# board.net
KiCad netlist of a schematic drawn in EAGLE
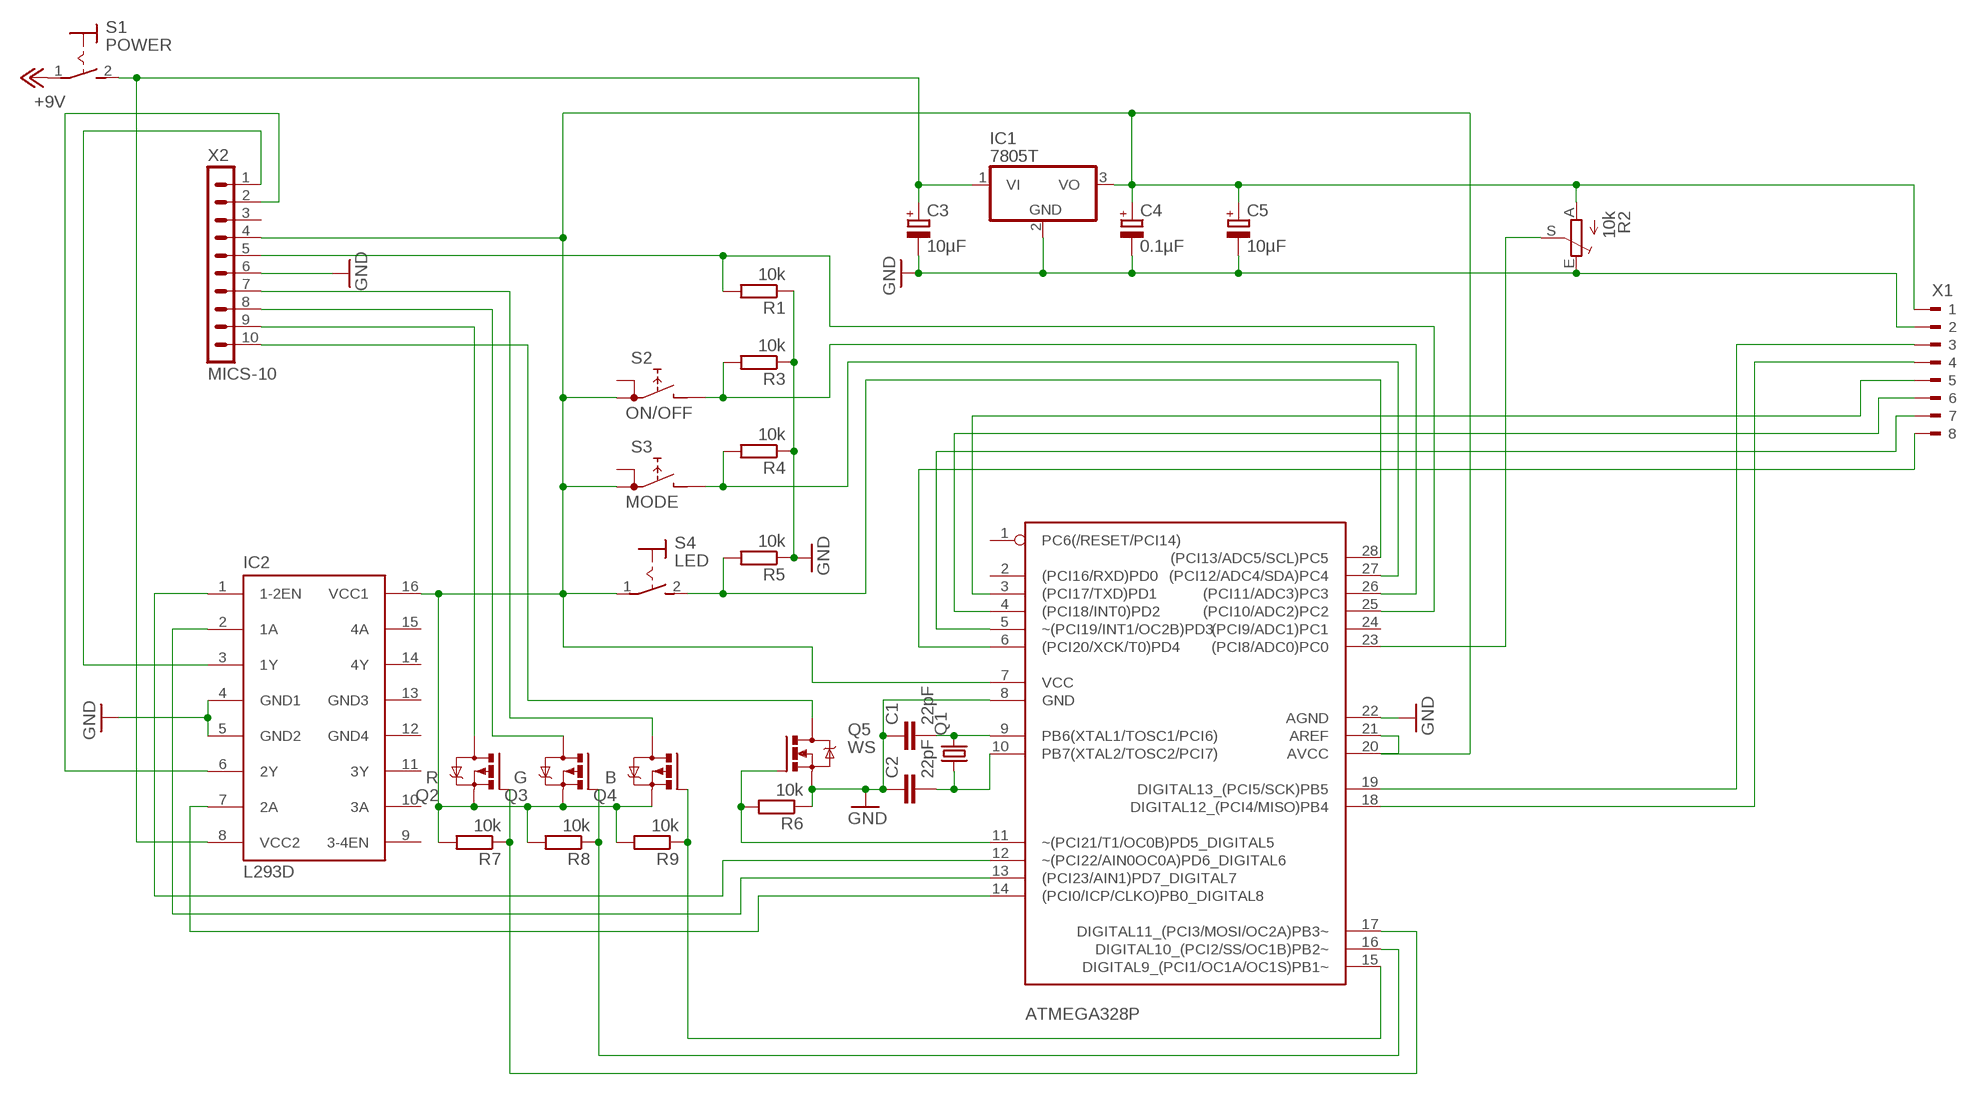
[diagram p0: schematic, sheet 1]

(export (version "E")
  (design (tool "Eeschema 10.0.6"))
  (components
    (comp (ref "ATMEGA328P")
      (value "ATMEGA328-20P")
      (footprint "eagle-import:DIL28-3")
      (libsource (lib "eagle-import") (part "ATMEGA328P-20"))
    )
    (comp (ref "C1")
      (value "22pF")
      (footprint "eagle-import:C2.5-2")
      (libsource (lib "eagle-import") (part "C2.5/2"))
    )
    (comp (ref "C2")
      (value "22pF")
      (footprint "eagle-import:C2.5-2")
      (libsource (lib "eagle-import") (part "C2.5/2"))
    )
    (comp (ref "C3")
      (value "10µF")
      (footprint "eagle-import:E2,5-5")
      (libsource (lib "eagle-import") (part "CPOL-EUE2.5-5"))
    )
    (comp (ref "C4")
      (value "0.1µF")
      (footprint "eagle-import:E2,5-5")
      (libsource (lib "eagle-import") (part "CPOL-EUE2.5-5"))
    )
    (comp (ref "C5")
      (value "10µF")
      (footprint "eagle-import:E2,5-5")
      (libsource (lib "eagle-import") (part "CPOL-EUE2.5-5"))
    )
    (comp (ref "IC1")
      (value "7805T")
      (footprint "eagle-import:TO220H")
      (libsource (lib "eagle-import") (part "78T05"))
    )
    (comp (ref "IC2")
      (value "L293D")
      (footprint "eagle-import:DIL16")
      (libsource (lib "eagle-import") (part "L293D"))
    )
    (comp (ref "Q1")
      (value "CRYSTALHC49S")
      (footprint "eagle-import:HC49_S")
      (libsource (lib "eagle-import") (part "CRYSTALHC49S"))
    )
    (comp (ref "Q2")
      (value "R")
      (footprint "eagle-import:I-PAK_TO251AA")
      (libsource (lib "eagle-import") (part "IRF?5305U"))
    )
    (comp (ref "Q3")
      (value "G")
      (footprint "eagle-import:I-PAK_TO251AA")
      (libsource (lib "eagle-import") (part "IRF?5305U"))
    )
    (comp (ref "Q4")
      (value "B")
      (footprint "eagle-import:I-PAK_TO251AA")
      (libsource (lib "eagle-import") (part "IRF?5305U"))
    )
    (comp (ref "Q5")
      (value "WS")
      (footprint "eagle-import:TO220BH")
      (libsource (lib "eagle-import") (part "IRFZ48Z"))
    )
    (comp (ref "R1")
      (value "10k")
      (footprint "eagle-import:0204_5")
      (libsource (lib "eagle-import") (part "R-EU_0204/5"))
    )
    (comp (ref "R2")
      (value "10k")
      (footprint "eagle-import:ECP10S")
      (libsource (lib "eagle-import") (part "TRIM_EU-ECP10S"))
    )
    (comp (ref "R3")
      (value "10k")
      (footprint "eagle-import:0204_5")
      (libsource (lib "eagle-import") (part "R-EU_0204/5"))
    )
    (comp (ref "R4")
      (value "10k")
      (footprint "eagle-import:0204_5")
      (libsource (lib "eagle-import") (part "R-EU_0204/5"))
    )
    (comp (ref "R5")
      (value "10k")
      (footprint "eagle-import:0204_5")
      (libsource (lib "eagle-import") (part "R-EU_0204/5"))
    )
    (comp (ref "R6")
      (value "10k")
      (footprint "eagle-import:0204_5")
      (libsource (lib "eagle-import") (part "R-EU_0204/5"))
    )
    (comp (ref "R7")
      (value "10k")
      (footprint "eagle-import:0204_5")
      (libsource (lib "eagle-import") (part "R-EU_0204/5"))
    )
    (comp (ref "R8")
      (value "10k")
      (footprint "eagle-import:0204_5")
      (libsource (lib "eagle-import") (part "R-EU_0204/5"))
    )
    (comp (ref "R9")
      (value "10k")
      (footprint "eagle-import:0204_5")
      (libsource (lib "eagle-import") (part "R-EU_0204/5"))
    )
    (comp (ref "S1")
      (value "POWER")
      (footprint "eagle-import:MS243")
      (libsource (lib "eagle-import") (part "MS243"))
    )
    (comp (ref "S2")
      (value "ON/OFF")
      (footprint "eagle-import:RDT1034")
      (libsource (lib "eagle-import") (part "RDT1034"))
    )
    (comp (ref "S3")
      (value "MODE")
      (footprint "eagle-import:RDT1034")
      (libsource (lib "eagle-import") (part "RDT1034"))
    )
    (comp (ref "S4")
      (value "LED")
      (footprint "eagle-import:MS243")
      (libsource (lib "eagle-import") (part "MS243"))
    )
    (comp (ref "X1")
      (value "90F-8")
      (footprint "eagle-import:90F-8")
      (libsource (lib "eagle-import") (part "90F-8"))
    )
    (comp (ref "X2")
      (value "MICS-10")
      (footprint "eagle-import:MICS-10")
      (libsource (lib "eagle-import") (part "MICS-10"))
    )
  )
  (nets
    (net (code "1") (name "+9V") (class "Default")
      (node (ref "S1") (pin "1") (pinfunction "P_1") (pintype "passive"))
    )
    (net (code "2") (name "/GND3") (class "Default")
      (node (ref "IC2") (pin "13") (pinfunction "GND3_13") (pintype "power_in"))
    )
    (net (code "3") (name "/GND4") (class "Default")
      (node (ref "IC2") (pin "12") (pinfunction "GND4_12") (pintype "power_in"))
    )
    (net (code "4") (name "GND") (class "Default")
      (node (ref "ATMEGA328P") (pin "22") (pinfunction "AGND_22") (pintype "bidirectional"))
      (node (ref "ATMEGA328P") (pin "8") (pinfunction "GND_8") (pintype "bidirectional"))
      (node (ref "C1") (pin "1") (pinfunction "1_1") (pintype "passive"))
      (node (ref "C2") (pin "1") (pinfunction "1_1") (pintype "passive"))
      (node (ref "C3") (pin "-") (pinfunction "-_-") (pintype "passive"))
      (node (ref "C4") (pin "-") (pinfunction "-_-") (pintype "passive"))
      (node (ref "C5") (pin "-") (pinfunction "-_-") (pintype "passive"))
      (node (ref "IC1") (pin "2") (pinfunction "GND_2") (pintype "passive"))
      (node (ref "IC2") (pin "4") (pinfunction "GND1_4") (pintype "power_in"))
      (node (ref "IC2") (pin "5") (pinfunction "GND2_5") (pintype "power_in"))
      (node (ref "Q5") (pin "S") (pinfunction "S_S") (pintype "passive"))
      (node (ref "R1") (pin "1") (pinfunction "1_1") (pintype "passive"))
      (node (ref "R2") (pin "E") (pinfunction "E_E") (pintype "passive"))
      (node (ref "R3") (pin "1") (pinfunction "1_1") (pintype "passive"))
      (node (ref "R4") (pin "1") (pinfunction "1_1") (pintype "passive"))
      (node (ref "R5") (pin "1") (pinfunction "1_1") (pintype "passive"))
      (node (ref "R6") (pin "1") (pinfunction "1_1") (pintype "passive"))
      (node (ref "X1") (pin "2") (pinfunction "2_2") (pintype "passive"))
      (node (ref "X2") (pin "6") (pinfunction "6_6") (pintype "passive"))
    )
    (net (code "5") (name "Net-(ATMEGA328P-(PCI0{slash}ICP{slash}CLKO)PB0_DIGITAL8)") (class "Default")
      (node (ref "ATMEGA328P") (pin "14") (pinfunction "(PCI0/ICP/CLKO)PB0_DIGITAL8_14") (pintype "bidirectional"))
      (node (ref "IC2") (pin "7") (pinfunction "2A_7") (pintype "input"))
    )
    (net (code "6") (name "Net-(ATMEGA328P-(PCI8{slash}ADC0)PC0)") (class "Default")
      (node (ref "ATMEGA328P") (pin "23") (pinfunction "(PCI8/ADC0)PC0_23") (pintype "bidirectional"))
      (node (ref "R2") (pin "S") (pinfunction "S_S") (pintype "passive"))
    )
    (net (code "7") (name "Net-(ATMEGA328P-(PCI10{slash}ADC2)PC2)") (class "Default")
      (node (ref "ATMEGA328P") (pin "25") (pinfunction "(PCI10/ADC2)PC2_25") (pintype "bidirectional"))
      (node (ref "R1") (pin "2") (pinfunction "2_2") (pintype "passive"))
      (node (ref "X2") (pin "5") (pinfunction "5_5") (pintype "passive"))
    )
    (net (code "8") (name "Net-(ATMEGA328P-(PCI11{slash}ADC3)PC3)") (class "Default")
      (node (ref "ATMEGA328P") (pin "26") (pinfunction "(PCI11/ADC3)PC3_26") (pintype "bidirectional"))
      (node (ref "R3") (pin "2") (pinfunction "2_2") (pintype "passive"))
      (node (ref "S2") (pin "B") (pinfunction "B_B") (pintype "passive"))
    )
    (net (code "9") (name "Net-(ATMEGA328P-(PCI12{slash}ADC4{slash}SDA)PC4)") (class "Default")
      (node (ref "ATMEGA328P") (pin "27") (pinfunction "(PCI12/ADC4/SDA)PC4_27") (pintype "bidirectional"))
      (node (ref "R4") (pin "2") (pinfunction "2_2") (pintype "passive"))
      (node (ref "S3") (pin "B") (pinfunction "B_B") (pintype "passive"))
    )
    (net (code "10") (name "Net-(ATMEGA328P-(PCI13{slash}ADC5{slash}SCL)PC5)") (class "Default")
      (node (ref "ATMEGA328P") (pin "28") (pinfunction "(PCI13/ADC5/SCL)PC5_28") (pintype "bidirectional"))
      (node (ref "R5") (pin "2") (pinfunction "2_2") (pintype "passive"))
      (node (ref "S4") (pin "2") (pinfunction "S_2") (pintype "passive"))
    )
    (net (code "11") (name "Net-(ATMEGA328P-(PCI17{slash}TXD)PD1)") (class "Default")
      (node (ref "ATMEGA328P") (pin "3") (pinfunction "(PCI17/TXD)PD1_3") (pintype "bidirectional"))
      (node (ref "X1") (pin "5") (pinfunction "5_5") (pintype "passive"))
    )
    (net (code "12") (name "Net-(ATMEGA328P-(PCI18{slash}INT0)PD2)") (class "Default")
      (node (ref "ATMEGA328P") (pin "4") (pinfunction "(PCI18/INT0)PD2_4") (pintype "bidirectional"))
      (node (ref "X1") (pin "6") (pinfunction "6_6") (pintype "passive"))
    )
    (net (code "13") (name "Net-(ATMEGA328P-(PCI20{slash}XCK{slash}T0)PD4)") (class "Default")
      (node (ref "ATMEGA328P") (pin "6") (pinfunction "(PCI20/XCK/T0)PD4_6") (pintype "bidirectional"))
      (node (ref "X1") (pin "8") (pinfunction "8_8") (pintype "passive"))
    )
    (net (code "14") (name "Net-(ATMEGA328P-(PCI23{slash}AIN1)PD7_DIGITAL7)") (class "Default")
      (node (ref "ATMEGA328P") (pin "13") (pinfunction "(PCI23/AIN1)PD7_DIGITAL7_13") (pintype "bidirectional"))
      (node (ref "IC2") (pin "2") (pinfunction "1A_2") (pintype "input"))
    )
    (net (code "15") (name "Net-(ATMEGA328P-AREF)") (class "Default")
      (node (ref "ATMEGA328P") (pin "20") (pinfunction "AVCC_20") (pintype "bidirectional"))
      (node (ref "ATMEGA328P") (pin "21") (pinfunction "AREF_21") (pintype "bidirectional"))
      (node (ref "ATMEGA328P") (pin "7") (pinfunction "VCC_7") (pintype "bidirectional"))
      (node (ref "C4") (pin "+") (pinfunction "+_+") (pintype "passive"))
      (node (ref "C5") (pin "+") (pinfunction "+_+") (pintype "passive"))
      (node (ref "IC1") (pin "3") (pinfunction "VO_3") (pintype "passive"))
      (node (ref "IC2") (pin "16") (pinfunction "VCC1_16") (pintype "power_in"))
      (node (ref "Q2") (pin "3") (pinfunction "S_3") (pintype "passive"))
      (node (ref "Q3") (pin "3") (pinfunction "S_3") (pintype "passive"))
      (node (ref "Q4") (pin "3") (pinfunction "S_3") (pintype "passive"))
      (node (ref "R2") (pin "A") (pinfunction "A_A") (pintype "passive"))
      (node (ref "R7") (pin "2") (pinfunction "2_2") (pintype "passive"))
      (node (ref "R8") (pin "2") (pinfunction "2_2") (pintype "passive"))
      (node (ref "R9") (pin "2") (pinfunction "2_2") (pintype "passive"))
      (node (ref "S2") (pin "A1") (pinfunction "A1_A1") (pintype "passive"))
      (node (ref "S3") (pin "A1") (pinfunction "A1_A1") (pintype "passive"))
      (node (ref "S4") (pin "1") (pinfunction "P_1") (pintype "passive"))
      (node (ref "X1") (pin "1") (pinfunction "1_1") (pintype "passive"))
      (node (ref "X2") (pin "4") (pinfunction "4_4") (pintype "passive"))
    )
    (net (code "16") (name "Net-(ATMEGA328P-DIGITAL9_(PCI1{slash}OC1A{slash}OC1S)PB1~{})") (class "Default")
      (node (ref "ATMEGA328P") (pin "15") (pinfunction "DIGITAL9_(PCI1/OC1A/OC1S)PB1~{}_15") (pintype "bidirectional"))
      (node (ref "Q4") (pin "1") (pinfunction "G_1") (pintype "passive"))
      (node (ref "R9") (pin "1") (pinfunction "1_1") (pintype "passive"))
    )
    (net (code "17") (name "Net-(ATMEGA328P-DIGITAL10_(PCI2{slash}SS{slash}OC1B)PB2~{})") (class "Default")
      (node (ref "ATMEGA328P") (pin "16") (pinfunction "DIGITAL10_(PCI2/SS/OC1B)PB2~{}_16") (pintype "bidirectional"))
      (node (ref "Q3") (pin "1") (pinfunction "G_1") (pintype "passive"))
      (node (ref "R8") (pin "1") (pinfunction "1_1") (pintype "passive"))
    )
    (net (code "18") (name "Net-(ATMEGA328P-DIGITAL11_(PCI3{slash}MOSI{slash}OC2A)PB3~{})") (class "Default")
      (node (ref "ATMEGA328P") (pin "17") (pinfunction "DIGITAL11_(PCI3/MOSI/OC2A)PB3~{}_17") (pintype "bidirectional"))
      (node (ref "Q2") (pin "1") (pinfunction "G_1") (pintype "passive"))
      (node (ref "R7") (pin "1") (pinfunction "1_1") (pintype "passive"))
    )
    (net (code "19") (name "Net-(ATMEGA328P-DIGITAL12_(PCI4{slash}MISO)PB4)") (class "Default")
      (node (ref "ATMEGA328P") (pin "18") (pinfunction "DIGITAL12_(PCI4/MISO)PB4_18") (pintype "bidirectional"))
      (node (ref "X1") (pin "4") (pinfunction "4_4") (pintype "passive"))
    )
    (net (code "20") (name "Net-(ATMEGA328P-DIGITAL13_(PCI5{slash}SCK)PB5)") (class "Default")
      (node (ref "ATMEGA328P") (pin "19") (pinfunction "DIGITAL13_(PCI5/SCK)PB5_19") (pintype "bidirectional"))
      (node (ref "X1") (pin "3") (pinfunction "3_3") (pintype "passive"))
    )
    (net (code "21") (name "Net-(ATMEGA328P-PB6(XTAL1{slash}TOSC1{slash}PCI6))") (class "Default")
      (node (ref "ATMEGA328P") (pin "9") (pinfunction "PB6(XTAL1/TOSC1/PCI6)_9") (pintype "bidirectional"))
      (node (ref "C1") (pin "2") (pinfunction "2_2") (pintype "passive"))
      (node (ref "Q1") (pin "2") (pinfunction "2_2") (pintype "passive"))
    )
    (net (code "22") (name "Net-(ATMEGA328P-PB7(XTAL2{slash}TOSC2{slash}PCI7))") (class "Default")
      (node (ref "ATMEGA328P") (pin "10") (pinfunction "PB7(XTAL2/TOSC2/PCI7)_10") (pintype "bidirectional"))
      (node (ref "C2") (pin "2") (pinfunction "2_2") (pintype "passive"))
      (node (ref "Q1") (pin "1") (pinfunction "1_1") (pintype "passive"))
    )
    (net (code "23") (name "Net-(ATMEGA328P-~{(PCI19{slash}INT1{slash}OC2B})PD3)") (class "Default")
      (node (ref "ATMEGA328P") (pin "5") (pinfunction "~{(PCI19/INT1/OC2B})PD3_5") (pintype "bidirectional"))
      (node (ref "X1") (pin "7") (pinfunction "7_7") (pintype "passive"))
    )
    (net (code "24") (name "Net-(ATMEGA328P-~{(PCI21{slash}T1{slash}OC0B})PD5_DIGITAL5)") (class "Default")
      (node (ref "ATMEGA328P") (pin "11") (pinfunction "~{(PCI21/T1/OC0B})PD5_DIGITAL5_11") (pintype "bidirectional"))
      (node (ref "Q5") (pin "G") (pinfunction "G_G") (pintype "passive"))
      (node (ref "R6") (pin "2") (pinfunction "2_2") (pintype "passive"))
    )
    (net (code "25") (name "Net-(ATMEGA328P-~{(PCI22{slash}AIN0OC0A})PD6_DIGITAL6)") (class "Default")
      (node (ref "ATMEGA328P") (pin "12") (pinfunction "~{(PCI22/AIN0OC0A})PD6_DIGITAL6_12") (pintype "bidirectional"))
      (node (ref "IC2") (pin "1") (pinfunction "1-2EN_1") (pintype "input"))
    )
    (net (code "26") (name "Net-(IC1-VI)") (class "Default")
      (node (ref "C3") (pin "+") (pinfunction "+_+") (pintype "passive"))
      (node (ref "IC1") (pin "1") (pinfunction "VI_1") (pintype "input"))
      (node (ref "IC2") (pin "8") (pinfunction "VCC2_8") (pintype "power_in"))
      (node (ref "S1") (pin "2") (pinfunction "S_2") (pintype "passive"))
    )
    (net (code "27") (name "Net-(IC2-1Y)") (class "Default")
      (node (ref "IC2") (pin "3") (pinfunction "1Y_3") (pintype "output"))
      (node (ref "X2") (pin "1") (pinfunction "1_1") (pintype "passive"))
    )
    (net (code "28") (name "Net-(IC2-2Y)") (class "Default")
      (node (ref "IC2") (pin "6") (pinfunction "2Y_6") (pintype "output"))
      (node (ref "X2") (pin "2") (pinfunction "2_2") (pintype "passive"))
    )
    (net (code "29") (name "Net-(Q2-D)") (class "Default")
      (node (ref "Q2") (pin "2") (pinfunction "D_2") (pintype "passive"))
      (node (ref "X2") (pin "9") (pinfunction "9_9") (pintype "passive"))
    )
    (net (code "30") (name "Net-(Q3-D)") (class "Default")
      (node (ref "Q3") (pin "2") (pinfunction "D_2") (pintype "passive"))
      (node (ref "X2") (pin "8") (pinfunction "8_8") (pintype "passive"))
    )
    (net (code "31") (name "Net-(Q4-D)") (class "Default")
      (node (ref "Q4") (pin "2") (pinfunction "D_2") (pintype "passive"))
      (node (ref "X2") (pin "7") (pinfunction "7_7") (pintype "passive"))
    )
    (net (code "32") (name "Net-(Q5-PadD)") (class "Default")
      (node (ref "Q5") (pin "D") (pinfunction "D_D") (pintype "passive"))
      (node (ref "X2") (pin "10") (pinfunction "10_10") (pintype "passive"))
    )
    (net (code "33") (name "unconnected-(ATMEGA328P-(PCI9{slash}ADC1)PC1-Pad24)") (class "Default")
      (node (ref "ATMEGA328P") (pin "24") (pinfunction "(PCI9/ADC1)PC1_24") (pintype "bidirectional"))
    )
    (net (code "34") (name "unconnected-(ATMEGA328P-(PCI16{slash}RXD)PD0-Pad2)") (class "Default")
      (node (ref "ATMEGA328P") (pin "2") (pinfunction "(PCI16/RXD)PD0_2") (pintype "bidirectional"))
    )
    (net (code "35") (name "unconnected-(ATMEGA328P-PC6({slash}RESET{slash}PCI14)-Pad1)") (class "Default")
      (node (ref "ATMEGA328P") (pin "1") (pinfunction "PC6(/RESET/PCI14)_1") (pintype "bidirectional"))
    )
    (net (code "36") (name "unconnected-(IC2-3-4EN-Pad9)") (class "Default")
      (node (ref "IC2") (pin "9") (pinfunction "3-4EN_9") (pintype "input"))
    )
    (net (code "37") (name "unconnected-(IC2-3A-Pad10)") (class "Default")
      (node (ref "IC2") (pin "10") (pinfunction "3A_10") (pintype "input"))
    )
    (net (code "38") (name "unconnected-(IC2-3Y-Pad11)") (class "Default")
      (node (ref "IC2") (pin "11") (pinfunction "3Y_11") (pintype "output"))
    )
    (net (code "39") (name "unconnected-(IC2-4A-Pad15)") (class "Default")
      (node (ref "IC2") (pin "15") (pinfunction "4A_15") (pintype "input"))
    )
    (net (code "40") (name "unconnected-(IC2-4Y-Pad14)") (class "Default")
      (node (ref "IC2") (pin "14") (pinfunction "4Y_14") (pintype "output"))
    )
    (net (code "41") (name "unconnected-(S2-PadA)") (class "Default")
      (node (ref "S2") (pin "A") (pinfunction "A_A") (pintype "passive"))
    )
    (net (code "42") (name "unconnected-(S3-PadA)") (class "Default")
      (node (ref "S3") (pin "A") (pinfunction "A_A") (pintype "passive"))
    )
    (net (code "43") (name "unconnected-(X2-Pad3)") (class "Default")
      (node (ref "X2") (pin "3") (pinfunction "3_3") (pintype "passive"))
    )
  )
)
